# Encoder.net
KiCad netlist of a schematic drawn in Altium Designer
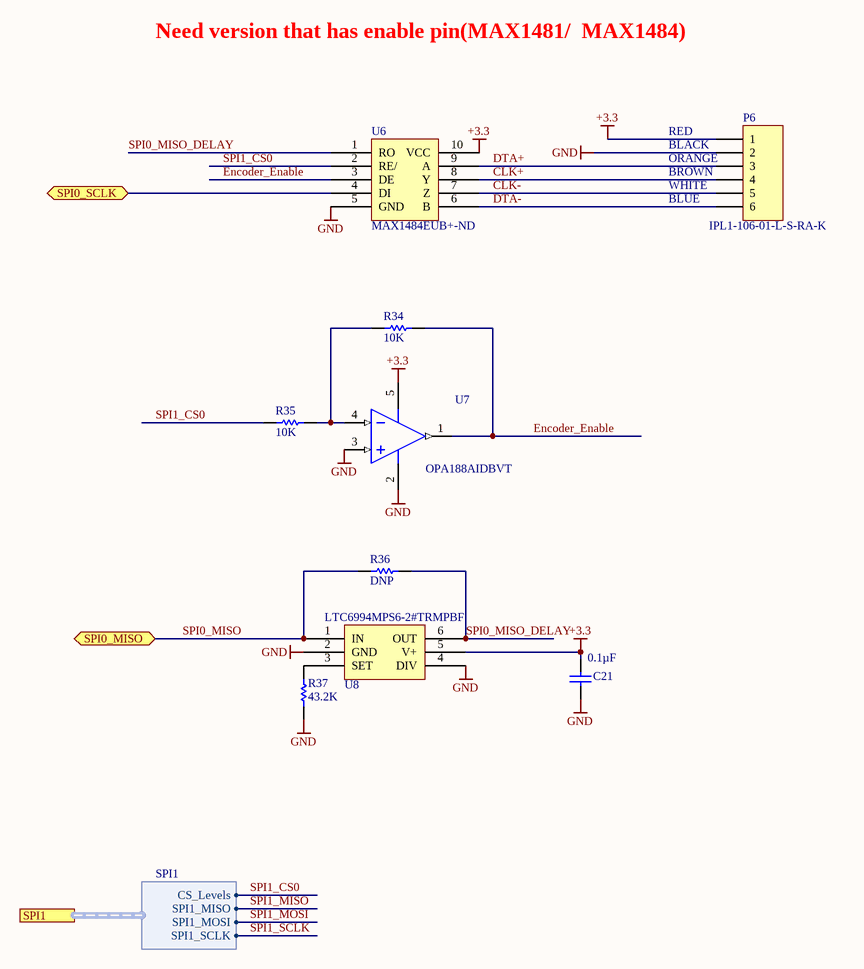
[diagram p0: Encoder.SchDoc]

(export (version "E")
  (design (tool "Eeschema 10.0.6"))
  (components
    (comp (ref "C21")
      (value "CAP CER 0.1UF 25V X7R 0805")
      (footprint "CAPC0805(2012)145_N")
      (fields
        (field (name "MANUFACTURER") "Murata Electronics North America")
        (field (name "MANUFACTURER PART NUMBER") "GRM21BR71E104KA01L")
        (field (name "CAPACITANCE") "0.1µF")
        (field (name "TOLERANCE") "±10%")
      )
      (libsource (lib "Altium Content Vault") (part "CMP-1036-04795-1"))
    )
    (comp (ref "P6")
      (value "IPL1-106-01-L-S-RA-K")
      (footprint "IPL1-106-01-L-S-RA-K")
      (description "Header, 6-Pin")
      (fields (field (name "MANUFACTURER") "Samtec Inc."))
      (libsource (lib "Miscellaneous Connectors") (part "Header 6"))
    )
    (comp (ref "R34")
      (value "10K")
      (footprint "RESC0805(2012)_L")
      (description "RES SMD 10K OHM 1% 1/8W 0805")
      (fields
        (field (name "MANUFACTURER") "Vishay Dale")
        (field (name "MANUFACTURER PART NUMBER") "CRCW080510K0FKEA")
      )
      (libsource (lib "Altium Content Vault") (part "CMP-1013-00215-1"))
    )
    (comp (ref "R35")
      (value "10K")
      (footprint "RESC0805(2012)_L")
      (description "RES SMD 10K OHM 1% 1/8W 0805")
      (fields
        (field (name "MANUFACTURER") "Vishay Dale")
        (field (name "MANUFACTURER PART NUMBER") "CRCW080510K0FKEA")
      )
      (libsource (lib "Altium Content Vault") (part "CMP-1013-00215-1"))
    )
    (comp (ref "R36")
      (value "DNP")
      (footprint "RESC0805(2012)_L")
      (description "RES SMD 0 OHM 5% 1/8W 0805")
      (libsource (lib "Altium Content Vault") (part "CMP-1013-00215-1"))
    )
    (comp (ref "R37")
      (value "43.2K")
      (footprint "RESC0805(2012)_L")
      (description "RES SMD 43.2K OHM 1% 1/8W 0805")
      (fields
        (field (name "MANUFACTURER") "Vishay Dale")
        (field (name "MANUFACTURER PART NUMBER") "CRCW080543K2FKEA")
      )
      (libsource (lib "Altium Content Vault") (part "CMP-1013-00215-1"))
    )
    (comp (ref "U6")
      (value "MAX1484EUB+")
      (footprint "MAX1486EUB+")
      (description "IC TXRX RS485/RS422 10-UMAX")
      (fields (field (name "SUPPLIER PART NUMBER 1") "MAX1484EUB+-ND"))
      (libsource (lib "ZLS_Schematic_lib") (part "MAX1484EUB+"))
    )
    (comp (ref "U7")
      (value "OPA188AIDBVT")
      (footprint "DBV0005A_L")
      (fields (field (name "MANUFACTURER") "Texas Instruments"))
      (libsource (lib "Altium Content Vault") (part "TI-OPA188-DBV5"))
    )
    (comp (ref "U8")
      (value "LTC6994MPS6-2#TRMPBF")
      (footprint "LTC6994MPS6-2#TRMPBF")
      (fields
        (field (name "MANUFACTURER") "Linear Technology/Analog Devices")
        (field (name "MANUFACTURER PART NUMBER") "LTC6994CS6-2#TRMPBF")
        (field (name "BASE PART NUMBER") "LTC6994")
      )
      (libsource (lib "ZLS_Schematic_lib") (part "LTC6994MPS6-2#TRMPBF"))
    )
  )
  (nets
    (net (code "2") (name "+3.3") (class "Default")
      (node (ref "C21") (pin "1") (pinfunction "1_1") (pintype "passive"))
      (node (ref "P6") (pin "1") (pinfunction "1_1") (pintype "passive"))
      (node (ref "U6") (pin "10") (pinfunction "VCC_10") (pintype "passive"))
      (node (ref "U7") (pin "5") (pinfunction "V+_5") (pintype "power_in"))
      (node (ref "U8") (pin "5") (pinfunction "V+_5") (pintype "passive"))
    )
    (net (code "3") (name "/CLK+") (class "Default")
      (node (ref "P6") (pin "4") (pinfunction "4_4") (pintype "passive"))
      (node (ref "U6") (pin "8") (pinfunction "Y_8") (pintype "passive"))
    )
    (net (code "4") (name "/CLK-") (class "Default")
      (node (ref "P6") (pin "5") (pinfunction "5_5") (pintype "passive"))
      (node (ref "U6") (pin "7") (pinfunction "Z_7") (pintype "passive"))
    )
    (net (code "5") (name "/DTA+") (class "Default")
      (node (ref "P6") (pin "3") (pinfunction "3_3") (pintype "passive"))
      (node (ref "U6") (pin "9") (pinfunction "A_9") (pintype "passive"))
    )
    (net (code "6") (name "/DTA-") (class "Default")
      (node (ref "P6") (pin "6") (pinfunction "6_6") (pintype "passive"))
      (node (ref "U6") (pin "6") (pinfunction "B_6") (pintype "passive"))
    )
    (net (code "7") (name "/Encoder_Enable") (class "Default")
      (node (ref "R34") (pin "2") (pinfunction "2_2") (pintype "passive"))
      (node (ref "U6") (pin "3") (pinfunction "DE_3") (pintype "passive"))
      (node (ref "U7") (pin "1") (pinfunction "OUT_1") (pintype "output"))
    )
    (net (code "8") (name "/SPI0_MISO") (class "Default")
      (node (ref "R36") (pin "1") (pinfunction "1_1") (pintype "passive"))
      (node (ref "U8") (pin "1") (pinfunction "IN_1") (pintype "passive"))
    )
    (net (code "9") (name "/SPI0_MISO_DELAY") (class "Default")
      (node (ref "R36") (pin "2") (pinfunction "2_2") (pintype "passive"))
      (node (ref "U6") (pin "1") (pinfunction "RO_1") (pintype "passive"))
      (node (ref "U8") (pin "6") (pinfunction "OUT_6") (pintype "passive"))
    )
    (net (code "10") (name "/SPI0_SCLK") (class "Default")
      (node (ref "U6") (pin "4") (pinfunction "DI_4") (pintype "passive"))
    )
    (net (code "11") (name "/SPI1_CS0") (class "Default")
      (node (ref "R35") (pin "1") (pinfunction "1_1") (pintype "passive"))
      (node (ref "U6") (pin "2") (pinfunction "RE/_2") (pintype "passive"))
    )
    (net (code "16") (name "GND") (class "Default")
      (node (ref "C21") (pin "2") (pinfunction "2_2") (pintype "passive"))
      (node (ref "P6") (pin "2") (pinfunction "2_2") (pintype "passive"))
      (node (ref "R37") (pin "2") (pinfunction "2_2") (pintype "passive"))
      (node (ref "U6") (pin "5") (pinfunction "GND_5") (pintype "passive"))
      (node (ref "U7") (pin "2") (pinfunction "V-_2") (pintype "power_in"))
      (node (ref "U7") (pin "3") (pinfunction "IN+_3") (pintype "input"))
      (node (ref "U8") (pin "2") (pinfunction "GND_2") (pintype "passive"))
      (node (ref "U8") (pin "4") (pinfunction "DIV_4") (pintype "passive"))
    )
    (net (code "17") (name "Net-(U7-IN-)") (class "Default")
      (node (ref "R34") (pin "1") (pinfunction "1_1") (pintype "passive"))
      (node (ref "R35") (pin "2") (pinfunction "2_2") (pintype "passive"))
      (node (ref "U7") (pin "4") (pinfunction "IN-_4") (pintype "input"))
    )
    (net (code "18") (name "Net-(U8-SET)") (class "Default")
      (node (ref "R37") (pin "1") (pinfunction "1_1") (pintype "passive"))
      (node (ref "U8") (pin "3") (pinfunction "SET_3") (pintype "passive"))
    )
  )
)
